# MCU_IMU.net
KiCad netlist of a schematic drawn in Altium Designer
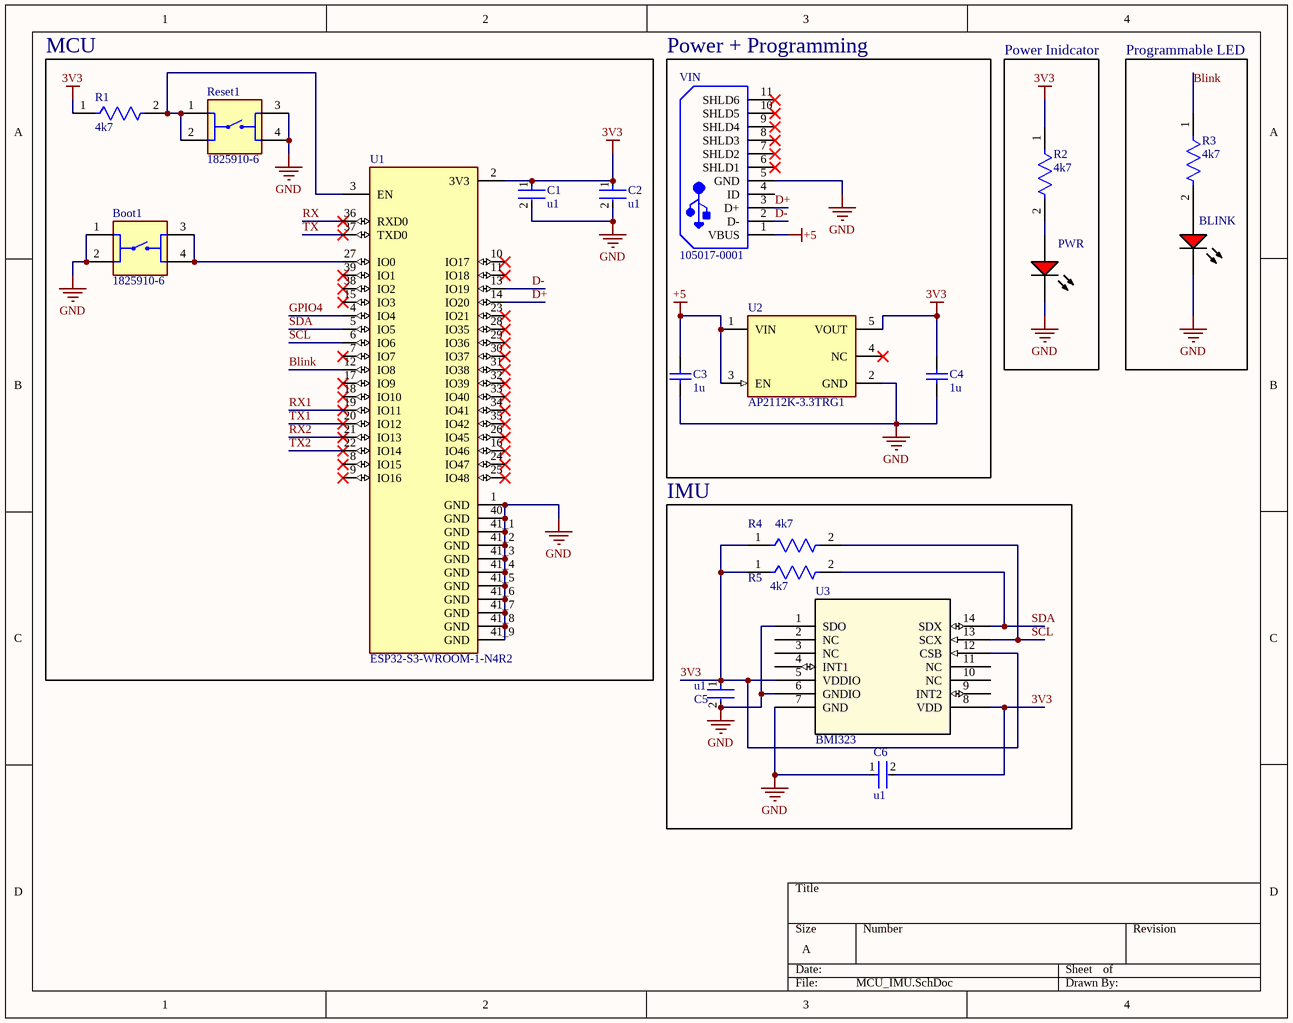
[diagram p0: MCU_IMU.SchDoc]

(export (version "E")
  (design (tool "Eeschema 10.0.6"))
  (components
    (comp (ref "BLINK")
      (value "SML-LX1206IC-TR")
      (footprint "LUMX-SML-LX1206IC_V")
      (description "LED Red, 65 mW, -40 to 85 degC, 2-Pin SMD, RoHS, Tape and Reel")
      (fields (field (name "MANUFACTURER") "Lumex"))
      (libsource (lib "Altium Content Vault") (part "LED-RED-AK-2"))
    )
    (comp (ref "Boot1")
      (value "1825910-6")
      (footprint "SW_1825910-6-4")
      (description "Switch Push Button OFF (ON) SPST Round Button 0.05A 24VDC Momentary Contact PC Pins Thru-Hole")
      (fields (field (name "MF") "TE Connectivity") (field (name "DIGI-KEY_PART_NUMBER") "450-1650-ND"))
      (libsource (lib "First") (part "1825910-6"))
    )
    (comp (ref "C1")
      (value "u1")
      (footprint "FP-CC0805-0_85-MFG")
      (description "CC0805KRX7R9BB104 CAP CER 0.1UF 50V X7R 0805")
      (fields (field (name "TOLERANCE") "0.1") (field (name "MANUFACTURER PART NUMBER") "CC0805KRX7R9BB104"))
      (libsource (lib "Altium Content Vault") (part "11868f565c42a9108669ba33697ecf6"))
    )
    (comp (ref "C2")
      (value "u1")
      (footprint "FP-CC0805-0_85-MFG")
      (description "CC0805KRX7R9BB104 CAP CER 0.1UF 50V X7R 0805")
      (fields (field (name "TOLERANCE") "0.1") (field (name "MANUFACTURER PART NUMBER") "CC0805KRX7R9BB104"))
      (libsource (lib "Altium Content Vault") (part "11868f565c42a9108669ba33697ecf6"))
    )
    (comp (ref "C3")
      (value "1u")
      (footprint "CAPC2013X140X50ML20T25")
      (fields (field (name "MANUFACTURER") "Kemet") (field (name "PART NUMBER") "C0805C105K5RACTU"))
      (libsource (lib "Altium Content Vault") (part "CAP"))
    )
    (comp (ref "C4")
      (value "1u")
      (footprint "CAPC2013X140X50ML20T25")
      (fields (field (name "MANUFACTURER") "Kemet") (field (name "PART NUMBER") "C0805C105K5RACTU"))
      (libsource (lib "Altium Content Vault") (part "CAP"))
    )
    (comp (ref "C5")
      (value "u1")
      (footprint "FP-CC0805-0_85-MFG")
      (description "CC0805KRX7R9BB104 CAP CER 0.1UF 50V X7R 0805")
      (fields (field (name "TOLERANCE") "0.1") (field (name "MANUFACTURER PART NUMBER") "CC0805KRX7R9BB104"))
      (libsource (lib "Altium Content Vault") (part "11868f565c42a9108669ba33697ecf6"))
    )
    (comp (ref "C6")
      (value "u1")
      (footprint "FP-CC0805-0_85-MFG")
      (description "CC0805KRX7R9BB104 CAP CER 0.1UF 50V X7R 0805")
      (fields (field (name "TOLERANCE") "0.1") (field (name "MANUFACTURER PART NUMBER") "CC0805KRX7R9BB104"))
      (libsource (lib "Altium Content Vault") (part "11868f565c42a9108669ba33697ecf6"))
    )
    (comp (ref "PWR")
      (value "SML-LX1206IC-TR")
      (footprint "LUMX-SML-LX1206IC_V")
      (description "LED Red, 65 mW, -40 to 85 degC, 2-Pin SMD, RoHS, Tape and Reel")
      (fields (field (name "MANUFACTURER") "Lumex"))
      (libsource (lib "Altium Content Vault") (part "LED-RED-AK-2"))
    )
    (comp (ref "R1")
      (value "4k7")
      (footprint "FP-CRCW0805-e3-IPC_B")
      (description "CRCW08054K70FKEARES Thick Film, 4.7kΩ, 1%, 0.125W, 100ppm/°C, 0805")
      (fields (field (name "TOLERANCE") "1%"))
      (libsource (lib "Altium Content Vault") (part "1029c3af85768c4190bb7ad29bc67b5"))
    )
    (comp (ref "R2")
      (value "4k7")
      (footprint "FP-CRCW0805-e3-IPC_B")
      (description "CRCW08054K70FKEARES Thick Film, 4.7kΩ, 1%, 0.125W, 100ppm/°C, 0805")
      (fields (field (name "TOLERANCE") "1%"))
      (libsource (lib "Altium Content Vault") (part "1029c3af85768c4190bb7ad29bc67b5"))
    )
    (comp (ref "R3")
      (value "4k7")
      (footprint "FP-CRCW0805-e3-IPC_B")
      (description "CRCW08054K70FKEARES Thick Film, 4.7kΩ, 1%, 0.125W, 100ppm/°C, 0805")
      (fields (field (name "TOLERANCE") "1%"))
      (libsource (lib "Altium Content Vault") (part "1029c3af85768c4190bb7ad29bc67b5"))
    )
    (comp (ref "R4")
      (value "4k7")
      (footprint "FP-CRCW0805-e3-IPC_B")
      (description "CRCW08054K70FKEARES Thick Film, 4.7kΩ, 1%, 0.125W, 100ppm/°C, 0805")
      (fields (field (name "TOLERANCE") "1%"))
      (libsource (lib "Altium Content Vault") (part "1029c3af85768c4190bb7ad29bc67b5"))
    )
    (comp (ref "R5")
      (value "4k7")
      (footprint "FP-CRCW0805-e3-IPC_B")
      (description "CRCW08054K70FKEARES Thick Film, 4.7kΩ, 1%, 0.125W, 100ppm/°C, 0805")
      (fields (field (name "TOLERANCE") "1%"))
      (libsource (lib "Altium Content Vault") (part "1029c3af85768c4190bb7ad29bc67b5"))
    )
    (comp (ref "Reset1")
      (value "1825910-6")
      (footprint "SW_1825910-6-4")
      (description "Switch Push Button OFF (ON) SPST Round Button 0.05A 24VDC Momentary Contact PC Pins Thru-Hole")
      (fields (field (name "MF") "TE Connectivity") (field (name "DIGI-KEY_PART_NUMBER") "450-1650-ND"))
      (libsource (lib "First") (part "1825910-6"))
    )
    (comp (ref "U1")
      (value "ESP32-S3-WROOM-1-N4R2")
      (footprint "XCVR_ESP32-S3-WROOM-1-N4R2")
      (description "Bluetooth, WiFi 802.11b/g/n, Bluetooth v5.0 Transceiver Module 2.4GHz PCB Trace Surface Mount")
      (fields (field (name "MF") "Espressif Systems"))
      (libsource (lib "ESP32-S3-WROOM-1-N4R2") (part "ESP32-S3-WROOM-1-N4R2"))
    )
    (comp (ref "U2")
      (value "AP2112K-3.3TRG1")
      (footprint "FP-SOT25-IPC_A")
      (description "IC REG LINEAR 3.3V 600MA SOT25")
      (libsource (lib "Altium Content Vault") (part "c8ab751aee5229183125ab046a11caa"))
    )
    (comp (ref "U3")
      (value "BMI323")
      (footprint "BMI323_BOS")
      (description "No Description Available")
      (fields (field (name "COPYRIGHT") "Copyright (C) 2025 Ultra Librarian. All rights reserved."))
      (libsource (lib "AI_Project_Library") (part "BMI323"))
    )
    (comp (ref "VIN")
      (value "105017-0001")
      (footprint "USB-MICRO-B_V")
      (fields (field (name "MANUFACTURER") "Molex"))
      (libsource (lib "Altium Content Vault") (part "USB-5-6SHLD"))
    )
  )
  (nets
    (net (code "1") (name "+5") (class "Default")
      (node (ref "C3") (pin "2") (pinfunction "2_2") (pintype "passive"))
      (node (ref "U2") (pin "1") (pinfunction "VIN_1") (pintype "power_in"))
      (node (ref "U2") (pin "3") (pinfunction "EN_3") (pintype "input"))
      (node (ref "VIN") (pin "1") (pinfunction "VBUS_1") (pintype "passive"))
    )
    (net (code "2") (name "/Blink") (class "Default")
      (node (ref "R3") (pin "1") (pinfunction "1_1") (pintype "passive"))
      (node (ref "U1") (pin "12") (pinfunction "IO8_12") (pintype "bidirectional"))
    )
    (net (code "3") (name "/D+") (class "Default")
      (node (ref "U1") (pin "14") (pinfunction "IO20_14") (pintype "bidirectional"))
      (node (ref "VIN") (pin "3") (pinfunction "D+_3") (pintype "passive"))
    )
    (net (code "4") (name "/D-") (class "Default")
      (node (ref "U1") (pin "13") (pinfunction "IO19_13") (pintype "bidirectional"))
      (node (ref "VIN") (pin "2") (pinfunction "D-_2") (pintype "passive"))
    )
    (net (code "5") (name "/GPIO4") (class "Default")
      (node (ref "U1") (pin "4") (pinfunction "IO4_4") (pintype "bidirectional"))
    )
    (net (code "6") (name "/RX") (class "Default")
      (node (ref "U1") (pin "36") (pinfunction "RXD0_36") (pintype "bidirectional+no_connect"))
    )
    (net (code "7") (name "/RX1") (class "Default")
      (node (ref "U1") (pin "19") (pinfunction "IO11_19") (pintype "bidirectional+no_connect"))
    )
    (net (code "8") (name "/RX2") (class "Default")
      (node (ref "U1") (pin "21") (pinfunction "IO13_21") (pintype "bidirectional+no_connect"))
    )
    (net (code "9") (name "/SCL") (class "Default")
      (node (ref "R4") (pin "2") (pinfunction "2_2") (pintype "passive"))
      (node (ref "U1") (pin "6") (pinfunction "IO6_6") (pintype "bidirectional"))
      (node (ref "U3") (pin "13") (pinfunction "SCX_13") (pintype "input"))
    )
    (net (code "10") (name "/SDA") (class "Default")
      (node (ref "R5") (pin "2") (pinfunction "2_2") (pintype "passive"))
      (node (ref "U1") (pin "5") (pinfunction "IO5_5") (pintype "bidirectional"))
      (node (ref "U3") (pin "14") (pinfunction "SDX_14") (pintype "bidirectional"))
    )
    (net (code "11") (name "/TX") (class "Default")
      (node (ref "U1") (pin "37") (pinfunction "TXD0_37") (pintype "bidirectional+no_connect"))
    )
    (net (code "12") (name "/TX1") (class "Default")
      (node (ref "U1") (pin "20") (pinfunction "IO12_20") (pintype "bidirectional+no_connect"))
    )
    (net (code "13") (name "/TX2") (class "Default")
      (node (ref "U1") (pin "22") (pinfunction "IO14_22") (pintype "bidirectional+no_connect"))
    )
    (net (code "14") (name "3V3") (class "Default")
      (node (ref "C1") (pin "1") (pinfunction "1_1") (pintype "passive"))
      (node (ref "C2") (pin "1") (pinfunction "1_1") (pintype "passive"))
      (node (ref "C4") (pin "2") (pinfunction "2_2") (pintype "passive"))
      (node (ref "C5") (pin "1") (pinfunction "1_1") (pintype "passive"))
      (node (ref "C6") (pin "2") (pinfunction "2_2") (pintype "passive"))
      (node (ref "R1") (pin "1") (pinfunction "1_1") (pintype "passive"))
      (node (ref "R2") (pin "1") (pinfunction "1_1") (pintype "passive"))
      (node (ref "R4") (pin "1") (pinfunction "1_1") (pintype "passive"))
      (node (ref "R5") (pin "1") (pinfunction "1_1") (pintype "passive"))
      (node (ref "U1") (pin "2") (pinfunction "3V3_2") (pintype "power_in"))
      (node (ref "U2") (pin "5") (pinfunction "VOUT_5") (pintype "power_in"))
      (node (ref "U3") (pin "12") (pinfunction "CSB_12") (pintype "input"))
      (node (ref "U3") (pin "5") (pinfunction "VDDIO_5") (pintype "power_in"))
      (node (ref "U3") (pin "8") (pinfunction "VDD_8") (pintype "power_in"))
    )
    (net (code "15") (name "GND") (class "Default")
      (node (ref "BLINK") (pin "2") (pinfunction "K_2") (pintype "passive"))
      (node (ref "Boot1") (pin "1") (pinfunction "1_1") (pintype "passive"))
      (node (ref "Boot1") (pin "2") (pinfunction "2_2") (pintype "passive"))
      (node (ref "C1") (pin "2") (pinfunction "2_2") (pintype "passive"))
      (node (ref "C2") (pin "2") (pinfunction "2_2") (pintype "passive"))
      (node (ref "C3") (pin "1") (pinfunction "1_1") (pintype "passive"))
      (node (ref "C4") (pin "1") (pinfunction "1_1") (pintype "passive"))
      (node (ref "C5") (pin "2") (pinfunction "2_2") (pintype "passive"))
      (node (ref "C6") (pin "1") (pinfunction "1_1") (pintype "passive"))
      (node (ref "PWR") (pin "2") (pinfunction "K_2") (pintype "passive"))
      (node (ref "Reset1") (pin "3") (pinfunction "3_3") (pintype "passive"))
      (node (ref "Reset1") (pin "4") (pinfunction "4_4") (pintype "passive"))
      (node (ref "U1") (pin "1") (pinfunction "GND_1") (pintype "power_in"))
      (node (ref "U1") (pin "40") (pinfunction "GND_40") (pintype "power_in"))
      (node (ref "U1") (pin "41_1") (pinfunction "GND_41_1") (pintype "power_in"))
      (node (ref "U1") (pin "41_2") (pinfunction "GND_41_2") (pintype "power_in"))
      (node (ref "U1") (pin "41_3") (pinfunction "GND_41_3") (pintype "power_in"))
      (node (ref "U1") (pin "41_4") (pinfunction "GND_41_4") (pintype "power_in"))
      (node (ref "U1") (pin "41_5") (pinfunction "GND_41_5") (pintype "power_in"))
      (node (ref "U1") (pin "41_6") (pinfunction "GND_41_6") (pintype "power_in"))
      (node (ref "U1") (pin "41_7") (pinfunction "GND_41_7") (pintype "power_in"))
      (node (ref "U1") (pin "41_8") (pinfunction "GND_41_8") (pintype "power_in"))
      (node (ref "U1") (pin "41_9") (pinfunction "GND_41_9") (pintype "power_in"))
      (node (ref "U2") (pin "2") (pinfunction "GND_2") (pintype "power_in"))
      (node (ref "U3") (pin "1") (pinfunction "SDO_1") (pintype "passive"))
      (node (ref "U3") (pin "6") (pinfunction "GNDIO_6") (pintype "power_in"))
      (node (ref "U3") (pin "7") (pinfunction "GND_7") (pintype "power_in"))
      (node (ref "VIN") (pin "5") (pinfunction "GND_5") (pintype "passive"))
    )
    (net (code "16") (name "Net-(BLINK-A)") (class "Default")
      (node (ref "BLINK") (pin "1") (pinfunction "A_1") (pintype "passive"))
      (node (ref "R3") (pin "2") (pinfunction "2_2") (pintype "passive"))
    )
    (net (code "17") (name "Net-(PWR-A)") (class "Default")
      (node (ref "PWR") (pin "1") (pinfunction "A_1") (pintype "passive"))
      (node (ref "R2") (pin "2") (pinfunction "2_2") (pintype "passive"))
    )
    (net (code "18") (name "Net-(U1-EN)") (class "Default")
      (node (ref "R1") (pin "2") (pinfunction "2_2") (pintype "passive"))
      (node (ref "Reset1") (pin "1") (pinfunction "1_1") (pintype "passive"))
      (node (ref "Reset1") (pin "2") (pinfunction "2_2") (pintype "passive"))
      (node (ref "U1") (pin "3") (pinfunction "EN_3") (pintype "power_in"))
    )
    (net (code "19") (name "Net-(U1-IO0)") (class "Default")
      (node (ref "Boot1") (pin "3") (pinfunction "3_3") (pintype "passive"))
      (node (ref "Boot1") (pin "4") (pinfunction "4_4") (pintype "passive"))
      (node (ref "U1") (pin "27") (pinfunction "IO0_27") (pintype "bidirectional"))
    )
    (net (code "20") (name "unconnected-(U1-IO1-Pad39)") (class "Default")
      (node (ref "U1") (pin "39") (pinfunction "IO1_39") (pintype "bidirectional+no_connect"))
    )
    (net (code "21") (name "unconnected-(U1-IO2-Pad38)") (class "Default")
      (node (ref "U1") (pin "38") (pinfunction "IO2_38") (pintype "bidirectional+no_connect"))
    )
    (net (code "22") (name "unconnected-(U1-IO3-Pad15)") (class "Default")
      (node (ref "U1") (pin "15") (pinfunction "IO3_15") (pintype "bidirectional+no_connect"))
    )
    (net (code "23") (name "unconnected-(U1-IO7-Pad7)") (class "Default")
      (node (ref "U1") (pin "7") (pinfunction "IO7_7") (pintype "bidirectional+no_connect"))
    )
    (net (code "24") (name "unconnected-(U1-IO9-Pad17)") (class "Default")
      (node (ref "U1") (pin "17") (pinfunction "IO9_17") (pintype "bidirectional+no_connect"))
    )
    (net (code "25") (name "unconnected-(U1-IO10-Pad18)") (class "Default")
      (node (ref "U1") (pin "18") (pinfunction "IO10_18") (pintype "bidirectional+no_connect"))
    )
    (net (code "26") (name "unconnected-(U1-IO15-Pad8)") (class "Default")
      (node (ref "U1") (pin "8") (pinfunction "IO15_8") (pintype "bidirectional+no_connect"))
    )
    (net (code "27") (name "unconnected-(U1-IO16-Pad9)") (class "Default")
      (node (ref "U1") (pin "9") (pinfunction "IO16_9") (pintype "bidirectional+no_connect"))
    )
    (net (code "28") (name "unconnected-(U1-IO17-Pad10)") (class "Default")
      (node (ref "U1") (pin "10") (pinfunction "IO17_10") (pintype "bidirectional+no_connect"))
    )
    (net (code "29") (name "unconnected-(U1-IO18-Pad11)") (class "Default")
      (node (ref "U1") (pin "11") (pinfunction "IO18_11") (pintype "bidirectional+no_connect"))
    )
    (net (code "30") (name "unconnected-(U1-IO21-Pad23)") (class "Default")
      (node (ref "U1") (pin "23") (pinfunction "IO21_23") (pintype "bidirectional+no_connect"))
    )
    (net (code "31") (name "unconnected-(U1-IO35-Pad28)") (class "Default")
      (node (ref "U1") (pin "28") (pinfunction "IO35_28") (pintype "bidirectional+no_connect"))
    )
    (net (code "32") (name "unconnected-(U1-IO36-Pad29)") (class "Default")
      (node (ref "U1") (pin "29") (pinfunction "IO36_29") (pintype "bidirectional+no_connect"))
    )
    (net (code "33") (name "unconnected-(U1-IO37-Pad30)") (class "Default")
      (node (ref "U1") (pin "30") (pinfunction "IO37_30") (pintype "bidirectional+no_connect"))
    )
    (net (code "34") (name "unconnected-(U1-IO38-Pad31)") (class "Default")
      (node (ref "U1") (pin "31") (pinfunction "IO38_31") (pintype "bidirectional+no_connect"))
    )
    (net (code "35") (name "unconnected-(U1-IO39-Pad32)") (class "Default")
      (node (ref "U1") (pin "32") (pinfunction "IO39_32") (pintype "bidirectional+no_connect"))
    )
    (net (code "36") (name "unconnected-(U1-IO40-Pad33)") (class "Default")
      (node (ref "U1") (pin "33") (pinfunction "IO40_33") (pintype "bidirectional+no_connect"))
    )
    (net (code "37") (name "unconnected-(U1-IO41-Pad34)") (class "Default")
      (node (ref "U1") (pin "34") (pinfunction "IO41_34") (pintype "bidirectional+no_connect"))
    )
    (net (code "38") (name "unconnected-(U1-IO42-Pad35)") (class "Default")
      (node (ref "U1") (pin "35") (pinfunction "IO42_35") (pintype "bidirectional+no_connect"))
    )
    (net (code "39") (name "unconnected-(U1-IO45-Pad26)") (class "Default")
      (node (ref "U1") (pin "26") (pinfunction "IO45_26") (pintype "bidirectional+no_connect"))
    )
    (net (code "40") (name "unconnected-(U1-IO46-Pad16)") (class "Default")
      (node (ref "U1") (pin "16") (pinfunction "IO46_16") (pintype "bidirectional+no_connect"))
    )
    (net (code "41") (name "unconnected-(U1-IO47-Pad24)") (class "Default")
      (node (ref "U1") (pin "24") (pinfunction "IO47_24") (pintype "bidirectional+no_connect"))
    )
    (net (code "42") (name "unconnected-(U1-IO48-Pad25)") (class "Default")
      (node (ref "U1") (pin "25") (pinfunction "IO48_25") (pintype "bidirectional+no_connect"))
    )
    (net (code "43") (name "unconnected-(U2-NC-Pad4)") (class "Default")
      (node (ref "U2") (pin "4") (pinfunction "NC_4") (pintype "passive+no_connect"))
    )
    (net (code "44") (name "unconnected-(U3-INT1-Pad4)") (class "Default")
      (node (ref "U3") (pin "4") (pinfunction "INT1_4") (pintype "bidirectional"))
    )
    (net (code "45") (name "unconnected-(U3-INT2-Pad9)") (class "Default")
      (node (ref "U3") (pin "9") (pinfunction "INT2_9") (pintype "bidirectional"))
    )
    (net (code "46") (name "unconnected-(U3-NC-Pad2)") (class "Default")
      (node (ref "U3") (pin "2") (pinfunction "NC_2") (pintype "passive"))
    )
    (net (code "47") (name "unconnected-(U3-NC-Pad3)") (class "Default")
      (node (ref "U3") (pin "3") (pinfunction "NC_3") (pintype "passive"))
    )
    (net (code "48") (name "unconnected-(U3-NC-Pad10)") (class "Default")
      (node (ref "U3") (pin "10") (pinfunction "NC_10") (pintype "passive"))
    )
    (net (code "49") (name "unconnected-(U3-NC-Pad11)") (class "Default")
      (node (ref "U3") (pin "11") (pinfunction "NC_11") (pintype "passive"))
    )
    (net (code "50") (name "unconnected-(VIN-ID-Pad4)") (class "Default")
      (node (ref "VIN") (pin "4") (pinfunction "ID_4") (pintype "passive"))
    )
    (net (code "51") (name "unconnected-(VIN-SHLD1-Pad6)") (class "Default")
      (node (ref "VIN") (pin "6") (pinfunction "SHLD1_6") (pintype "passive+no_connect"))
    )
    (net (code "52") (name "unconnected-(VIN-SHLD2-Pad7)") (class "Default")
      (node (ref "VIN") (pin "7") (pinfunction "SHLD2_7") (pintype "passive+no_connect"))
    )
    (net (code "53") (name "unconnected-(VIN-SHLD3-Pad8)") (class "Default")
      (node (ref "VIN") (pin "8") (pinfunction "SHLD3_8") (pintype "passive+no_connect"))
    )
    (net (code "54") (name "unconnected-(VIN-SHLD4-Pad9)") (class "Default")
      (node (ref "VIN") (pin "9") (pinfunction "SHLD4_9") (pintype "passive+no_connect"))
    )
    (net (code "55") (name "unconnected-(VIN-SHLD5-Pad10)") (class "Default")
      (node (ref "VIN") (pin "10") (pinfunction "SHLD5_10") (pintype "passive+no_connect"))
    )
    (net (code "56") (name "unconnected-(VIN-SHLD6-Pad11)") (class "Default")
      (node (ref "VIN") (pin "11") (pinfunction "SHLD6_11") (pintype "passive+no_connect"))
    )
  )
)
